# MCP73871_Solar.net
KiCad netlist of a schematic drawn in EAGLE
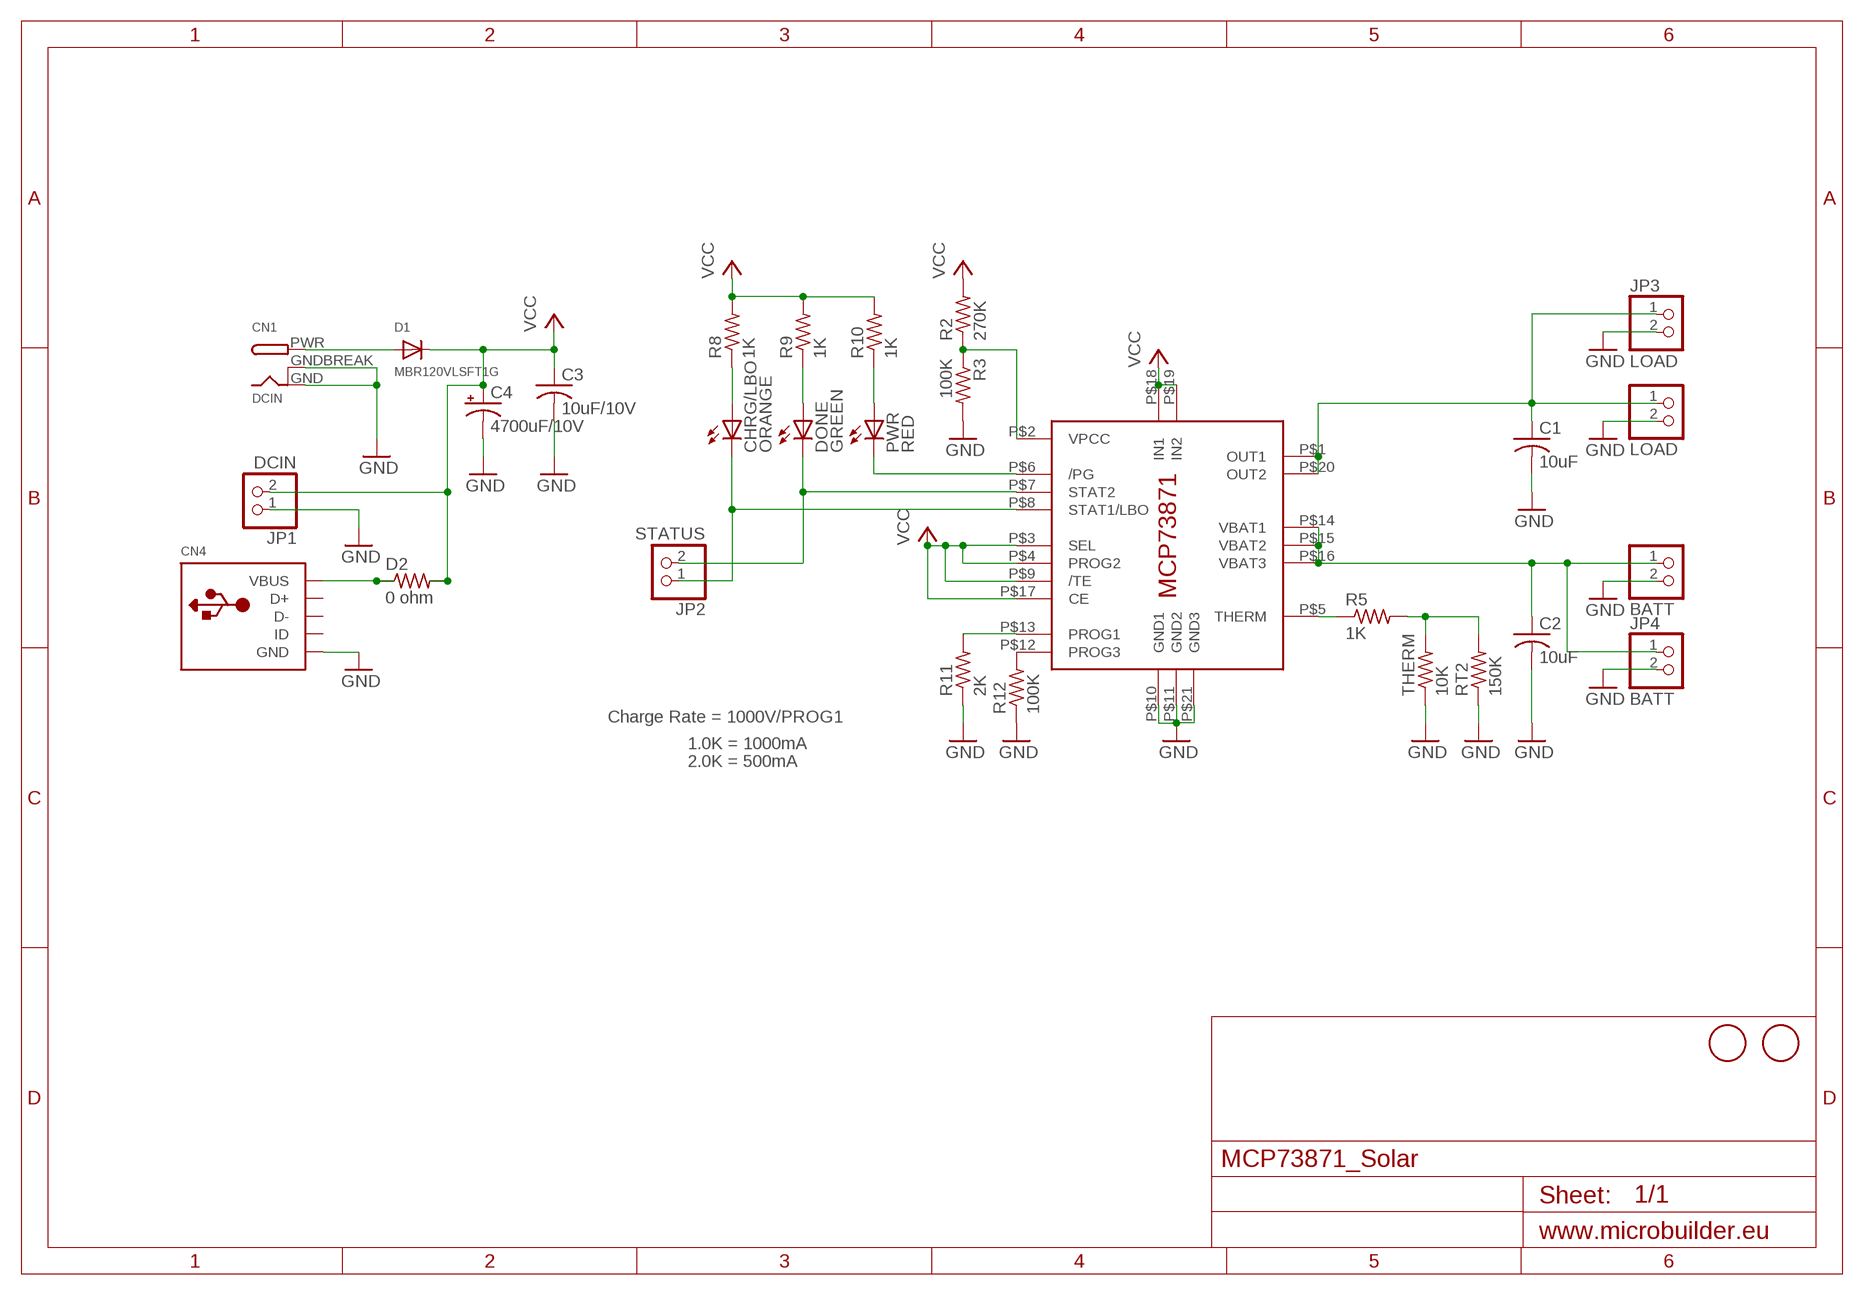
[diagram p0: schematic, sheet 1]

(export (version "E")
  (design (tool "Eeschema 10.0.6"))
  (components
    (comp (ref "BATT")
      (value "JST_2PIN-SMT-RA")
      (footprint "eagle-import:JST-PH-2-SMT-RA")
      (libsource (lib "eagle-import") (part "JST_2PIN-SMT-RA"))
    )
    (comp (ref "C1")
      (value "10uF")
      (footprint "eagle-import:C0805K")
      (libsource (lib "eagle-import") (part "C-USC0805K"))
    )
    (comp (ref "C2")
      (value "10uF")
      (footprint "eagle-import:C0805K")
      (libsource (lib "eagle-import") (part "C-USC0805K"))
    )
    (comp (ref "C3")
      (value "10uF/10V")
      (footprint "eagle-import:C0805K")
      (libsource (lib "eagle-import") (part "C-USC0805K"))
    )
    (comp (ref "C4")
      (value "4700uF/10V")
      (footprint "eagle-import:E5-13")
      (libsource (lib "eagle-import") (part "CPOL-USE5-13"))
    )
    (comp (ref "CHRG/LBO")
      (value "ORANGE")
      (footprint "eagle-import:CHIP-LED0805")
      (libsource (lib "eagle-import") (part "LEDCHIP-LED0805"))
    )
    (comp (ref "CN1")
      (value "DCIN")
      (footprint "eagle-import:DCJACK_1.3MM_PTH")
      (libsource (lib "eagle-import") (part "DCBARREL1.3MM"))
    )
    (comp (ref "CN4")
      (value "USBMINIB")
      (footprint "eagle-import:USB-MINIB")
      (libsource (lib "eagle-import") (part "USBMINIB"))
    )
    (comp (ref "D1")
      (value "MBR120VLSFT1G")
      (footprint "eagle-import:SOD-123")
      (libsource (lib "eagle-import") (part "DIODESOD-123"))
    )
    (comp (ref "D2")
      (value "0 ohm")
      (footprint "eagle-import:R0805")
      (libsource (lib "eagle-import") (part "R-US_R0805"))
    )
    (comp (ref "DONE")
      (value "GREEN")
      (footprint "eagle-import:CHIP-LED0805")
      (libsource (lib "eagle-import") (part "LEDCHIP-LED0805"))
    )
    (comp (ref "IC1")
      (value "MCP73871")
      (footprint "eagle-import:QFN20_4MM")
      (libsource (lib "eagle-import") (part "MCP73871"))
    )
    (comp (ref "JP1")
      (value "DCIN")
      (footprint "eagle-import:1X02_OVAL")
      (libsource (lib "eagle-import") (part "HEADER-1X2"))
    )
    (comp (ref "JP2")
      (value "STATUS")
      (footprint "eagle-import:1X02_OVAL")
      (libsource (lib "eagle-import") (part "HEADER-1X2"))
    )
    (comp (ref "JP3")
      (value "LOAD")
      (footprint "eagle-import:1X02_OVAL")
      (libsource (lib "eagle-import") (part "HEADER-1X2"))
    )
    (comp (ref "JP4")
      (value "BATT")
      (footprint "eagle-import:1X02_OVAL")
      (libsource (lib "eagle-import") (part "HEADER-1X2"))
    )
    (comp (ref "LOAD")
      (value "JST_2PIN-SMT-RA")
      (footprint "eagle-import:JST-PH-2-SMT-RA")
      (libsource (lib "eagle-import") (part "JST_2PIN-SMT-RA"))
    )
    (comp (ref "PWR")
      (value "RED")
      (footprint "eagle-import:CHIP-LED0805")
      (libsource (lib "eagle-import") (part "LEDCHIP-LED0805"))
    )
    (comp (ref "R2")
      (value "270K")
      (footprint "eagle-import:R0805")
      (libsource (lib "eagle-import") (part "R-US_R0805"))
    )
    (comp (ref "R3")
      (value "100K")
      (footprint "eagle-import:R0805")
      (libsource (lib "eagle-import") (part "R-US_R0805"))
    )
    (comp (ref "R5")
      (value "1K")
      (footprint "eagle-import:M0805")
      (libsource (lib "eagle-import") (part "R-US_M0805"))
    )
    (comp (ref "R8")
      (value "1K")
      (footprint "eagle-import:R0805")
      (libsource (lib "eagle-import") (part "R-US_R0805"))
    )
    (comp (ref "R9")
      (value "1K")
      (footprint "eagle-import:R0805")
      (libsource (lib "eagle-import") (part "R-US_R0805"))
    )
    (comp (ref "R10")
      (value "1K")
      (footprint "eagle-import:R0805")
      (libsource (lib "eagle-import") (part "R-US_R0805"))
    )
    (comp (ref "R11")
      (value "2K")
      (footprint "eagle-import:0805-THM")
      (libsource (lib "eagle-import") (part "R-US_FLIPFLOP"))
    )
    (comp (ref "R12")
      (value "100K")
      (footprint "eagle-import:R0805")
      (libsource (lib "eagle-import") (part "R-US_R0805"))
    )
    (comp (ref "RT2")
      (value "150K")
      (footprint "eagle-import:M0805")
      (libsource (lib "eagle-import") (part "R-US_M0805"))
    )
    (comp (ref "THERM")
      (value "10K")
      (footprint "eagle-import:0805-THM")
      (libsource (lib "eagle-import") (part "R-US_FLIPFLOP"))
    )
    (comp (ref "U$2")
      (value "FIDUCIAL")
      (footprint "eagle-import:FIDUCIAL_1MM")
      (libsource (lib "eagle-import") (part "FIDUCIAL"))
    )
    (comp (ref "U$3")
      (value "FIDUCIAL")
      (footprint "eagle-import:FIDUCIAL_1MM")
      (libsource (lib "eagle-import") (part "FIDUCIAL"))
    )
  )
  (nets
    (net (code "1") (name "GND") (class "Default")
      (node (ref "BATT") (pin "2") (pinfunction "1_2") (pintype "passive"))
      (node (ref "C1") (pin "2") (pinfunction "2_2") (pintype "passive"))
      (node (ref "C2") (pin "2") (pinfunction "2_2") (pintype "passive"))
      (node (ref "C3") (pin "2") (pinfunction "2_2") (pintype "passive"))
      (node (ref "C4") (pin "-") (pinfunction "-_-") (pintype "passive"))
      (node (ref "CN1") (pin "GND") (pinfunction "GND_GND") (pintype "power_in"))
      (node (ref "CN1") (pin "GNDBREAK") (pinfunction "GNDBREAK_GNDBREAK") (pintype "power_in"))
      (node (ref "CN4") (pin "GND") (pinfunction "GND_GND") (pintype "power_in"))
      (node (ref "IC1") (pin "P$10") (pinfunction "GND1_P$10") (pintype "power_in"))
      (node (ref "IC1") (pin "P$11") (pinfunction "GND2_P$11") (pintype "power_in"))
      (node (ref "IC1") (pin "P$21") (pinfunction "GND3_P$21") (pintype "power_in"))
      (node (ref "JP1") (pin "1") (pinfunction "1_1") (pintype "passive"))
      (node (ref "JP3") (pin "2") (pinfunction "2_2") (pintype "passive"))
      (node (ref "JP4") (pin "2") (pinfunction "2_2") (pintype "passive"))
      (node (ref "LOAD") (pin "2") (pinfunction "1_2") (pintype "passive"))
      (node (ref "R11") (pin "1") (pinfunction "1_1") (pintype "passive"))
      (node (ref "R12") (pin "1") (pinfunction "1_1") (pintype "passive"))
      (node (ref "R3") (pin "2") (pinfunction "2_2") (pintype "passive"))
      (node (ref "RT2") (pin "1") (pinfunction "1_1") (pintype "passive"))
      (node (ref "THERM") (pin "1") (pinfunction "1_1") (pintype "passive"))
    )
    (net (code "2") (name "Net-(BATT-2)") (class "Default")
      (node (ref "BATT") (pin "1") (pinfunction "2_1") (pintype "passive"))
      (node (ref "C2") (pin "1") (pinfunction "1_1") (pintype "passive"))
      (node (ref "IC1") (pin "P$14") (pinfunction "VBAT1_P$14") (pintype "output"))
      (node (ref "IC1") (pin "P$15") (pinfunction "VBAT2_P$15") (pintype "output"))
      (node (ref "IC1") (pin "P$16") (pinfunction "VBAT3_P$16") (pintype "output"))
      (node (ref "JP4") (pin "1") (pinfunction "1_1") (pintype "passive"))
    )
    (net (code "3") (name "Net-(CHRG/LBO-PadA)") (class "Default")
      (node (ref "CHRG/LBO") (pin "A") (pinfunction "A_A") (pintype "passive"))
      (node (ref "R8") (pin "1") (pinfunction "1_1") (pintype "passive"))
    )
    (net (code "4") (name "Net-(CN1-PadPWR)") (class "Default")
      (node (ref "CN1") (pin "PWR") (pinfunction "PWR_PWR") (pintype "power_in"))
      (node (ref "D1") (pin "A") (pinfunction "A_A") (pintype "passive"))
    )
    (net (code "5") (name "Net-(CN4-PadVBUS)") (class "Default")
      (node (ref "CN4") (pin "VBUS") (pinfunction "VBUS_VBUS") (pintype "power_in"))
      (node (ref "D2") (pin "1") (pinfunction "1_1") (pintype "passive"))
    )
    (net (code "6") (name "Net-(DONE-PadA)") (class "Default")
      (node (ref "DONE") (pin "A") (pinfunction "A_A") (pintype "passive"))
      (node (ref "R9") (pin "1") (pinfunction "1_1") (pintype "passive"))
    )
    (net (code "7") (name "Net-(IC1-OUT1)") (class "Default")
      (node (ref "C1") (pin "1") (pinfunction "1_1") (pintype "passive"))
      (node (ref "IC1") (pin "P$1") (pinfunction "OUT1_P$1") (pintype "output"))
      (node (ref "IC1") (pin "P$20") (pinfunction "OUT2_P$20") (pintype "output"))
      (node (ref "JP3") (pin "1") (pinfunction "1_1") (pintype "passive"))
      (node (ref "LOAD") (pin "1") (pinfunction "2_1") (pintype "passive"))
    )
    (net (code "8") (name "Net-(IC1-PROG1)") (class "Default")
      (node (ref "IC1") (pin "P$13") (pinfunction "PROG1_P$13") (pintype "input"))
      (node (ref "R11") (pin "2") (pinfunction "2_2") (pintype "passive"))
    )
    (net (code "9") (name "Net-(IC1-PROG3)") (class "Default")
      (node (ref "IC1") (pin "P$12") (pinfunction "PROG3_P$12") (pintype "input"))
      (node (ref "R12") (pin "2") (pinfunction "2_2") (pintype "passive"))
    )
    (net (code "10") (name "Net-(IC1-STAT1{slash}LBO)") (class "Default")
      (node (ref "CHRG/LBO") (pin "C") (pinfunction "C_C") (pintype "passive"))
      (node (ref "IC1") (pin "P$8") (pinfunction "STAT1/LBO_P$8") (pintype "output"))
      (node (ref "JP2") (pin "1") (pinfunction "1_1") (pintype "passive"))
    )
    (net (code "11") (name "Net-(IC1-STAT2)") (class "Default")
      (node (ref "DONE") (pin "C") (pinfunction "C_C") (pintype "passive"))
      (node (ref "IC1") (pin "P$7") (pinfunction "STAT2_P$7") (pintype "output"))
      (node (ref "JP2") (pin "2") (pinfunction "2_2") (pintype "passive"))
    )
    (net (code "12") (name "Net-(IC1-THERM)") (class "Default")
      (node (ref "IC1") (pin "P$5") (pinfunction "THERM_P$5") (pintype "input"))
      (node (ref "R5") (pin "1") (pinfunction "1_1") (pintype "passive"))
    )
    (net (code "13") (name "Net-(IC1-VPCC)") (class "Default")
      (node (ref "IC1") (pin "P$2") (pinfunction "VPCC_P$2") (pintype "input"))
      (node (ref "R2") (pin "1") (pinfunction "1_1") (pintype "passive"))
      (node (ref "R3") (pin "1") (pinfunction "1_1") (pintype "passive"))
    )
    (net (code "14") (name "Net-(IC1-{slash}PG)") (class "Default")
      (node (ref "IC1") (pin "P$6") (pinfunction "/PG_P$6") (pintype "output"))
      (node (ref "PWR") (pin "C") (pinfunction "C_C") (pintype "passive"))
    )
    (net (code "15") (name "Net-(PWR-PadA)") (class "Default")
      (node (ref "PWR") (pin "A") (pinfunction "A_A") (pintype "passive"))
      (node (ref "R10") (pin "1") (pinfunction "1_1") (pintype "passive"))
    )
    (net (code "16") (name "Net-(R5-Pad2)") (class "Default")
      (node (ref "R5") (pin "2") (pinfunction "2_2") (pintype "passive"))
      (node (ref "RT2") (pin "2") (pinfunction "2_2") (pintype "passive"))
      (node (ref "THERM") (pin "2") (pinfunction "2_2") (pintype "passive"))
    )
    (net (code "17") (name "VCC") (class "Default")
      (node (ref "C3") (pin "1") (pinfunction "1_1") (pintype "passive"))
      (node (ref "C4") (pin "+") (pinfunction "+_+") (pintype "passive"))
      (node (ref "D1") (pin "C") (pinfunction "C_C") (pintype "passive"))
      (node (ref "D2") (pin "2") (pinfunction "2_2") (pintype "passive"))
      (node (ref "IC1") (pin "P$17") (pinfunction "CE_P$17") (pintype "input"))
      (node (ref "IC1") (pin "P$18") (pinfunction "IN1_P$18") (pintype "input"))
      (node (ref "IC1") (pin "P$19") (pinfunction "IN2_P$19") (pintype "input"))
      (node (ref "IC1") (pin "P$3") (pinfunction "SEL_P$3") (pintype "input"))
      (node (ref "IC1") (pin "P$4") (pinfunction "PROG2_P$4") (pintype "input"))
      (node (ref "IC1") (pin "P$9") (pinfunction "/TE_P$9") (pintype "input"))
      (node (ref "JP1") (pin "2") (pinfunction "2_2") (pintype "passive"))
      (node (ref "R10") (pin "2") (pinfunction "2_2") (pintype "passive"))
      (node (ref "R2") (pin "2") (pinfunction "2_2") (pintype "passive"))
      (node (ref "R8") (pin "2") (pinfunction "2_2") (pintype "passive"))
      (node (ref "R9") (pin "2") (pinfunction "2_2") (pintype "passive"))
    )
    (net (code "18") (name "unconnected-(CN4-PadD+)") (class "Default")
      (node (ref "CN4") (pin "D+") (pinfunction "D+_D+") (pintype "bidirectional"))
    )
    (net (code "19") (name "unconnected-(CN4-PadD-)") (class "Default")
      (node (ref "CN4") (pin "D-") (pinfunction "D-_D-") (pintype "bidirectional"))
    )
    (net (code "20") (name "unconnected-(CN4-PadID)") (class "Default")
      (node (ref "CN4") (pin "ID") (pinfunction "ID_ID") (pintype "bidirectional"))
    )
  )
)
